# EDA.net
KiCad netlist of a schematic drawn in EasyEDA
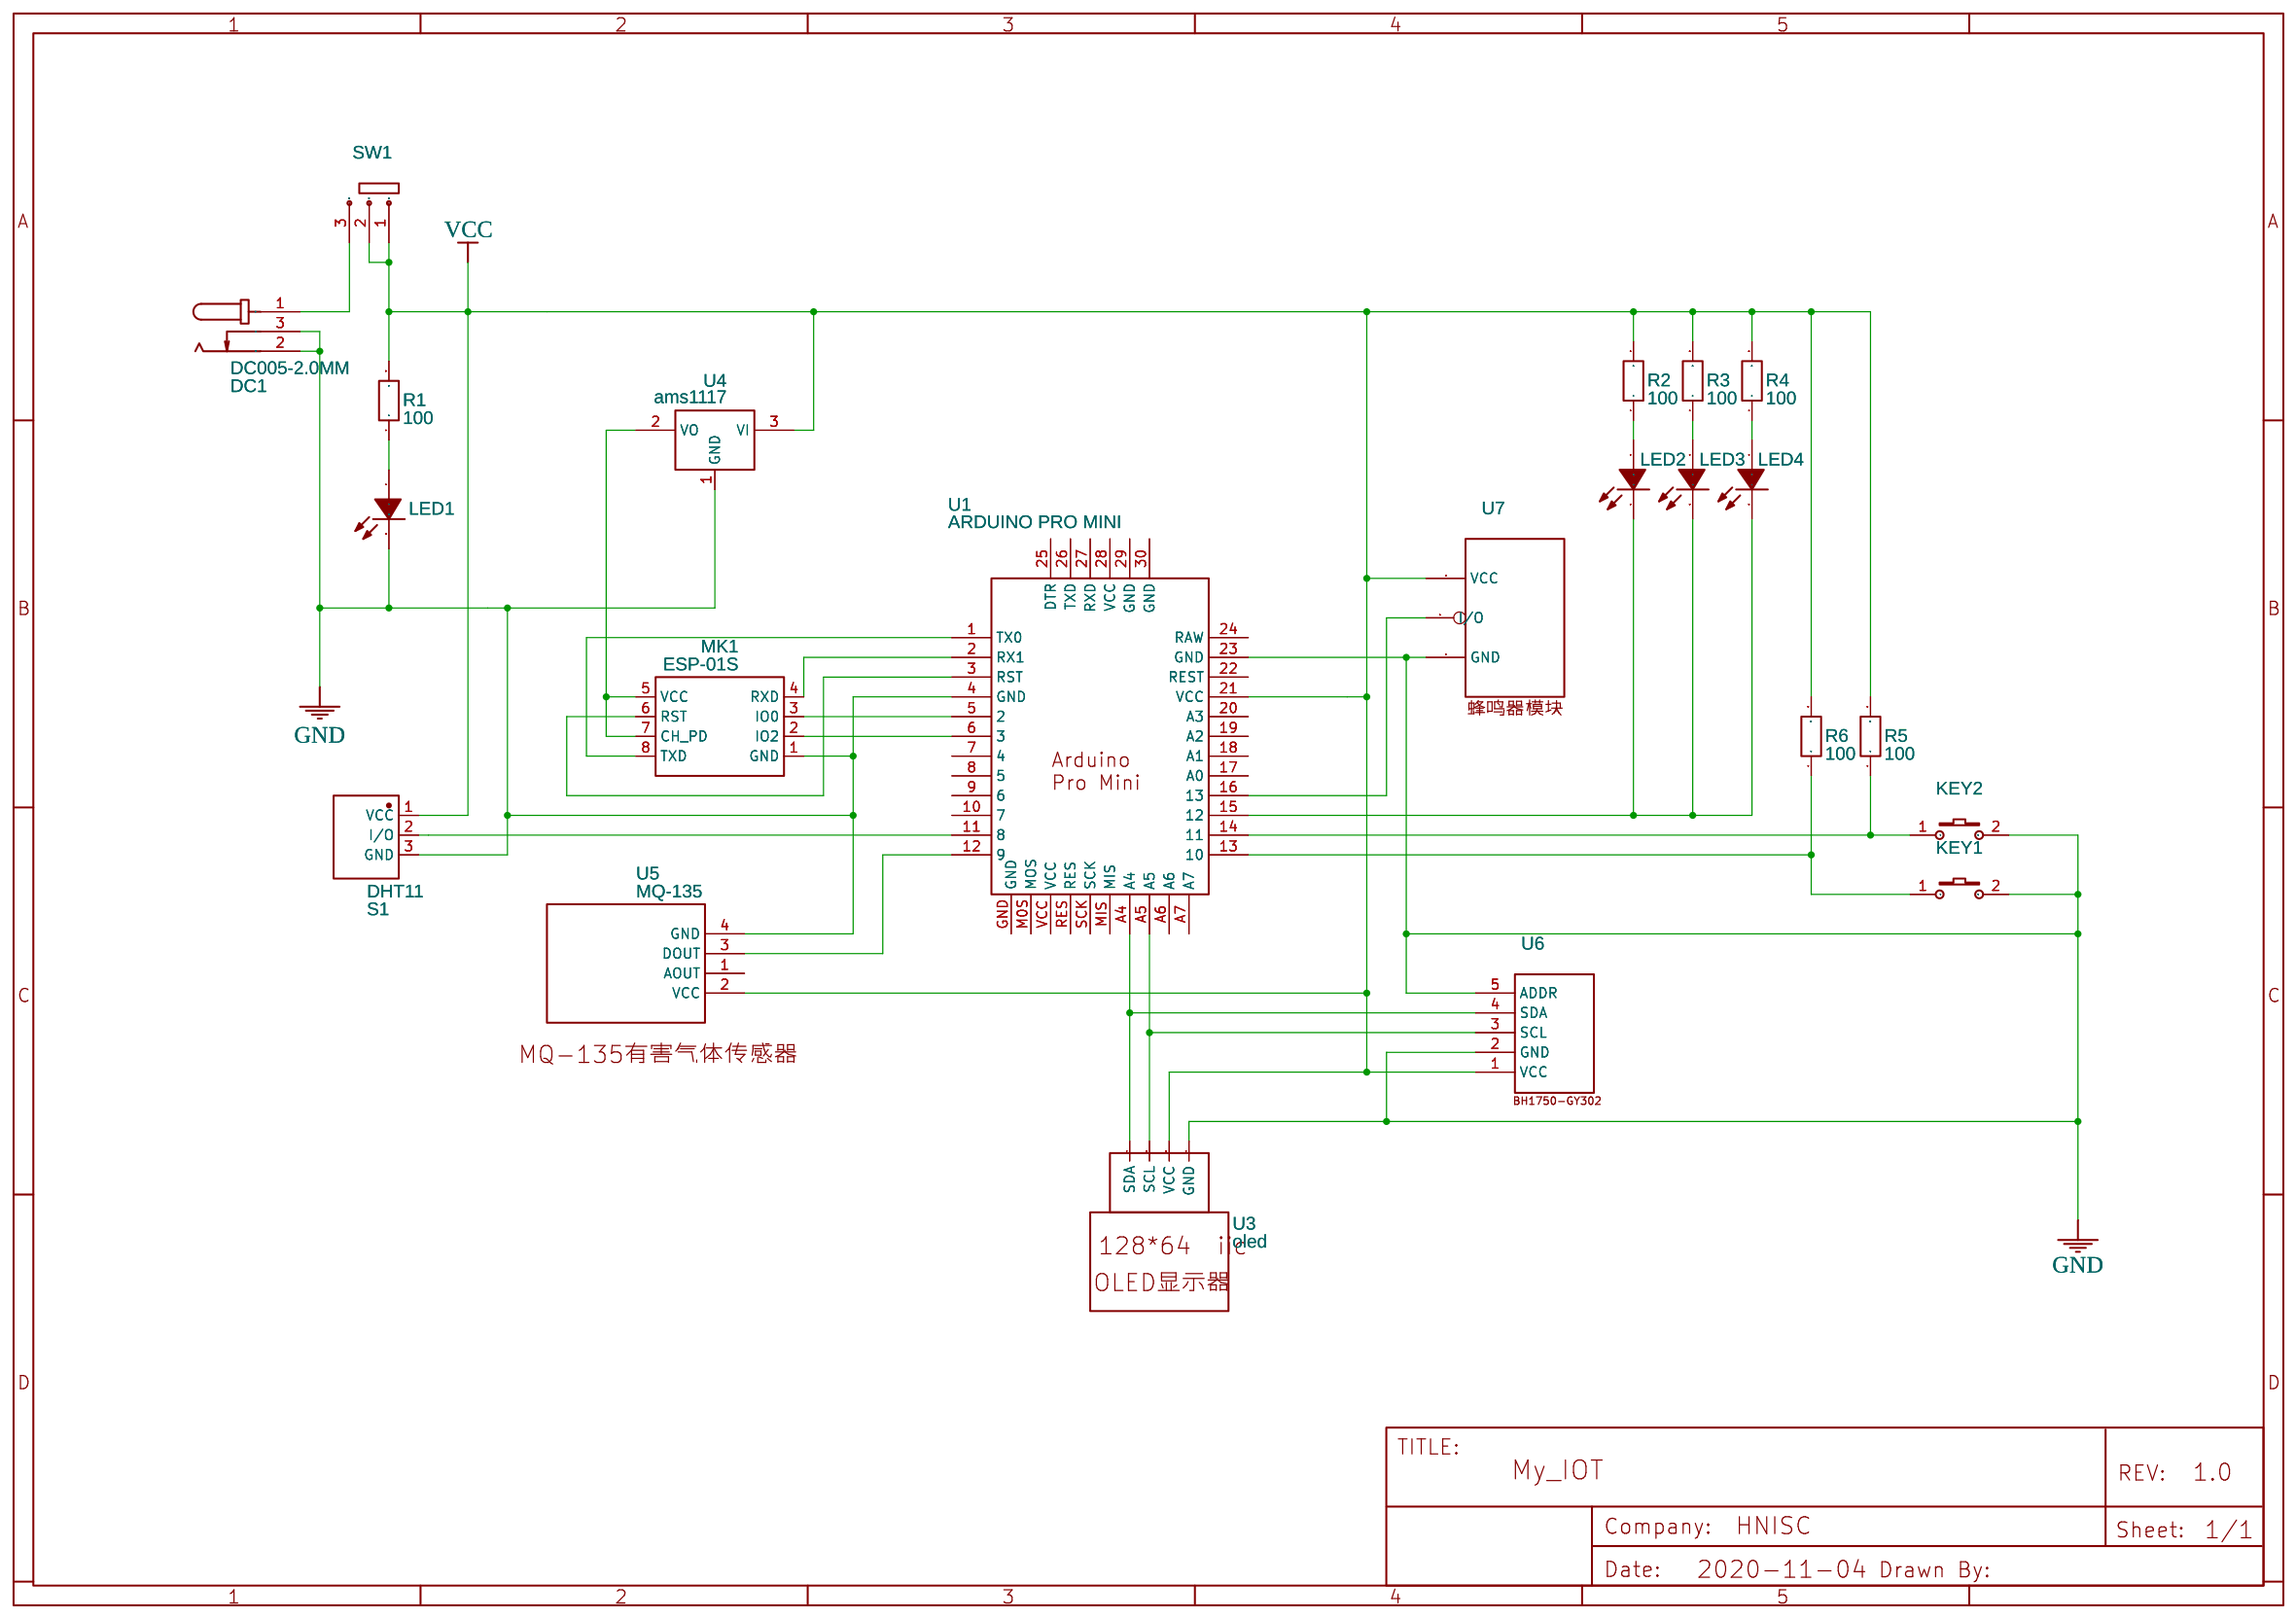
[diagram p0: schematic sheet]

(export (version "E")
  (design (tool "Eeschema 10.0.6"))
  (components
    (comp (ref "DC1")
      (value "DC005-2.0MM")
      (fields (field (name "BOM_Supplier Part") "C111567"))
      (libsource (lib "") (part "DC005-2.0MM"))
    )
    (comp (ref "KEY1")
      (value "K2-3.6×6.1_SMD")
      (fields
        (field (name "BOM_Manufacturer Part") "K2-1107ST-A4SW-06")
        (field (name "BOM_Supplier Part") "C118141")
      )
      (libsource (lib "") (part "K2-3.6×6.1_SMD"))
    )
    (comp (ref "KEY2")
      (value "K2-3.6×6.1_SMD")
      (fields
        (field (name "BOM_Manufacturer Part") "K2-1107ST-A4SW-06")
        (field (name "BOM_Supplier Part") "C118141")
      )
      (libsource (lib "") (part "K2-3.6×6.1_SMD"))
    )
    (comp (ref "LED1")
      (value "11-21/G6C-FN2P2B/2T")
      (fields (field (name "BOM_Supplier Part") "C264319"))
      (libsource (lib "") (part "11-21/G6C-FN2P2B/2T"))
    )
    (comp (ref "LED2")
      (value "11-21/G6C-FN2P2B/2T")
      (fields (field (name "BOM_Supplier Part") "C264319"))
      (libsource (lib "") (part "11-21/G6C-FN2P2B/2T"))
    )
    (comp (ref "LED3")
      (value "11-21/G6C-FN2P2B/2T")
      (fields (field (name "BOM_Supplier Part") "C264319"))
      (libsource (lib "") (part "11-21/G6C-FN2P2B/2T"))
    )
    (comp (ref "LED4")
      (value "11-21/G6C-FN2P2B/2T")
      (fields (field (name "BOM_Supplier Part") "C264319"))
      (libsource (lib "") (part "11-21/G6C-FN2P2B/2T"))
    )
    (comp (ref "MK1")
      (value "ESP-01S")
      (fields (field (name "BOM_Supplier Part") "C82893"))
      (libsource (lib "") (part "ESP-01S"))
    )
    (comp (ref "R1") (value "100") (libsource (lib "") (part "R_0603_EU")))
    (comp (ref "R2") (value "100") (libsource (lib "") (part "R_0603_EU")))
    (comp (ref "R3") (value "100") (libsource (lib "") (part "R_0603_EU")))
    (comp (ref "R4") (value "100") (libsource (lib "") (part "R_0603_EU")))
    (comp (ref "R5") (value "100") (libsource (lib "") (part "R_0603_EU")))
    (comp (ref "R6") (value "100") (libsource (lib "") (part "R_0603_EU")))
    (comp (ref "S1")
      (value "DHT11")
      (fields (field (name "BOM_Supplier Part") "E87032"))
      (libsource (lib "") (part "DHT11"))
    )
    (comp (ref "SW1")
      (value "K3-1235S-L1")
      (fields (field (name "BOM_Supplier Part") "C223838"))
      (libsource (lib "") (part "K3-1235S-L1"))
    )
    (comp (ref "U1")
      (value "ARDUINO PRO MINI")
      (fields (field (name "BOM_Manufacturer Part") "Arduino Pro Mini China"))
      (libsource (lib "") (part "ARDUINO PRO MINI"))
    )
    (comp (ref "U3") (value "oled") (libsource (lib "") (part "oled")))
    (comp (ref "U4") (value "ams1117") (libsource (lib "") (part "ams1117")))
    (comp (ref "U5") (value "MQ-135") (libsource (lib "") (part "MQ-135")))
    (comp (ref "U6") (value "BH1750光照度传感器") (libsource (lib "") (part "BH1750光照度传感器")))
    (comp (ref "U7") (value "蜂鸣器") (libsource (lib "") (part "蜂鸣器")))
  )
  (nets
    (net (code "1") (name "GND") (class "Default")
      (node (ref "DC1") (pin "2") (pinfunction "2_2") (pintype "unspecified"))
      (node (ref "DC1") (pin "3") (pinfunction "3_3") (pintype "unspecified"))
      (node (ref "KEY1") (pin "2") (pinfunction "2_2") (pintype "unspecified"))
      (node (ref "KEY2") (pin "2") (pinfunction "2_2") (pintype "unspecified"))
      (node (ref "LED1") (pin "2") (pinfunction "K_2") (pintype "unspecified"))
      (node (ref "MK1") (pin "1") (pinfunction "GND_1") (pintype "unspecified"))
      (node (ref "S1") (pin "3") (pinfunction "GND_3") (pintype "unspecified"))
      (node (ref "U1") (pin "23") (pinfunction "GND_23") (pintype "unspecified"))
      (node (ref "U1") (pin "4") (pinfunction "GND_4") (pintype "unspecified"))
      (node (ref "U3") (pin "1") (pinfunction "GND_1") (pintype "unspecified"))
      (node (ref "U4") (pin "1") (pinfunction "GND_1") (pintype "input"))
      (node (ref "U5") (pin "4") (pinfunction "GND_4") (pintype "unspecified"))
      (node (ref "U6") (pin "2") (pinfunction "GND_2") (pintype "unspecified"))
      (node (ref "U6") (pin "5") (pinfunction "ADDR_5") (pintype "unspecified"))
      (node (ref "U7") (pin "1") (pinfunction "GND_1") (pintype "unspecified"))
    )
    (net (code "2") (name "Net-(DC1-Pad1)") (class "Default")
      (node (ref "DC1") (pin "1") (pinfunction "1_1") (pintype "unspecified"))
      (node (ref "SW1") (pin "3") (pinfunction "3_3") (pintype "unspecified"))
    )
    (net (code "3") (name "Net-(LED1-A)") (class "Default")
      (node (ref "LED1") (pin "1") (pinfunction "A_1") (pintype "unspecified"))
      (node (ref "R1") (pin "1") (pinfunction "1_1") (pintype "unspecified"))
    )
    (net (code "4") (name "Net-(LED2-A)") (class "Default")
      (node (ref "LED2") (pin "1") (pinfunction "A_1") (pintype "unspecified"))
      (node (ref "R2") (pin "1") (pinfunction "1_1") (pintype "unspecified"))
    )
    (net (code "5") (name "Net-(LED2-K)") (class "Default")
      (node (ref "LED2") (pin "2") (pinfunction "K_2") (pintype "unspecified"))
      (node (ref "LED3") (pin "2") (pinfunction "K_2") (pintype "unspecified"))
      (node (ref "LED4") (pin "2") (pinfunction "K_2") (pintype "unspecified"))
      (node (ref "U1") (pin "15") (pinfunction "12_15") (pintype "unspecified"))
    )
    (net (code "6") (name "Net-(LED3-A)") (class "Default")
      (node (ref "LED3") (pin "1") (pinfunction "A_1") (pintype "unspecified"))
      (node (ref "R3") (pin "1") (pinfunction "1_1") (pintype "unspecified"))
    )
    (net (code "7") (name "Net-(LED4-A)") (class "Default")
      (node (ref "LED4") (pin "1") (pinfunction "A_1") (pintype "unspecified"))
      (node (ref "R4") (pin "1") (pinfunction "1_1") (pintype "unspecified"))
    )
    (net (code "8") (name "Net-(MK1-CH_PD)") (class "Default")
      (node (ref "MK1") (pin "5") (pinfunction "VCC_5") (pintype "unspecified"))
      (node (ref "MK1") (pin "7") (pinfunction "CH_PD_7") (pintype "unspecified"))
      (node (ref "U4") (pin "2") (pinfunction "VO_2") (pintype "unspecified"))
    )
    (net (code "9") (name "Net-(MK1-IO0)") (class "Default")
      (node (ref "MK1") (pin "3") (pinfunction "IO0_3") (pintype "unspecified"))
      (node (ref "U1") (pin "5") (pinfunction "2_5") (pintype "unspecified"))
    )
    (net (code "10") (name "Net-(MK1-IO2)") (class "Default")
      (node (ref "MK1") (pin "2") (pinfunction "IO2_2") (pintype "unspecified"))
      (node (ref "U1") (pin "6") (pinfunction "3_6") (pintype "unspecified"))
    )
    (net (code "11") (name "Net-(MK1-RST)") (class "Default")
      (node (ref "MK1") (pin "6") (pinfunction "RST_6") (pintype "unspecified"))
      (node (ref "U1") (pin "3") (pinfunction "RST_3") (pintype "unspecified"))
    )
    (net (code "12") (name "Net-(MK1-RXD)") (class "Default")
      (node (ref "MK1") (pin "4") (pinfunction "RXD_4") (pintype "unspecified"))
      (node (ref "U1") (pin "2") (pinfunction "RX1_2") (pintype "unspecified"))
    )
    (net (code "13") (name "Net-(MK1-TXD)") (class "Default")
      (node (ref "MK1") (pin "8") (pinfunction "TXD_8") (pintype "unspecified"))
      (node (ref "U1") (pin "1") (pinfunction "TX0_1") (pintype "unspecified"))
    )
    (net (code "14") (name "Net-(S1-I{slash}O)") (class "Default")
      (node (ref "S1") (pin "2") (pinfunction "I/O_2") (pintype "unspecified"))
      (node (ref "U1") (pin "11") (pinfunction "8_11") (pintype "unspecified"))
    )
    (net (code "15") (name "Net-(U1-9)") (class "Default")
      (node (ref "U1") (pin "12") (pinfunction "9_12") (pintype "unspecified"))
      (node (ref "U5") (pin "3") (pinfunction "DOUT_3") (pintype "unspecified"))
    )
    (net (code "16") (name "Net-(U1-10)") (class "Default")
      (node (ref "KEY1") (pin "1") (pinfunction "1_1") (pintype "unspecified"))
      (node (ref "R6") (pin "1") (pinfunction "1_1") (pintype "unspecified"))
      (node (ref "U1") (pin "13") (pinfunction "10_13") (pintype "unspecified"))
    )
    (net (code "17") (name "Net-(U1-11)") (class "Default")
      (node (ref "KEY2") (pin "1") (pinfunction "1_1") (pintype "unspecified"))
      (node (ref "R5") (pin "1") (pinfunction "1_1") (pintype "unspecified"))
      (node (ref "U1") (pin "14") (pinfunction "11_14") (pintype "unspecified"))
    )
    (net (code "18") (name "Net-(U1-13)") (class "Default")
      (node (ref "U1") (pin "16") (pinfunction "13_16") (pintype "unspecified"))
      (node (ref "U7") (pin "2") (pinfunction "I/O_2") (pintype "unspecified"))
    )
    (net (code "19") (name "Net-(U3-SCL)") (class "Default")
      (node (ref "U1") (pin "A5") (pinfunction "A5_A5") (pintype "unspecified"))
      (node (ref "U3") (pin "3") (pinfunction "SCL_3") (pintype "unspecified"))
      (node (ref "U6") (pin "3") (pinfunction "SCL_3") (pintype "unspecified"))
    )
    (net (code "20") (name "Net-(U3-SDA)") (class "Default")
      (node (ref "U1") (pin "A4") (pinfunction "A4_A4") (pintype "unspecified"))
      (node (ref "U3") (pin "4") (pinfunction "SDA_4") (pintype "unspecified"))
      (node (ref "U6") (pin "4") (pinfunction "SDA_4") (pintype "unspecified"))
    )
    (net (code "21") (name "VCC") (class "Default")
      (node (ref "R1") (pin "2") (pinfunction "2_2") (pintype "unspecified"))
      (node (ref "R2") (pin "2") (pinfunction "2_2") (pintype "unspecified"))
      (node (ref "R3") (pin "2") (pinfunction "2_2") (pintype "unspecified"))
      (node (ref "R4") (pin "2") (pinfunction "2_2") (pintype "unspecified"))
      (node (ref "R5") (pin "2") (pinfunction "2_2") (pintype "unspecified"))
      (node (ref "R6") (pin "2") (pinfunction "2_2") (pintype "unspecified"))
      (node (ref "S1") (pin "1") (pinfunction "VCC_1") (pintype "unspecified"))
      (node (ref "SW1") (pin "1") (pinfunction "1_1") (pintype "unspecified"))
      (node (ref "SW1") (pin "2") (pinfunction "2_2") (pintype "unspecified"))
      (node (ref "U1") (pin "21") (pinfunction "VCC_21") (pintype "unspecified"))
      (node (ref "U3") (pin "2") (pinfunction "VCC_2") (pintype "unspecified"))
      (node (ref "U4") (pin "3") (pinfunction "VI_3") (pintype "input"))
      (node (ref "U5") (pin "2") (pinfunction "VCC_2") (pintype "unspecified"))
      (node (ref "U6") (pin "1") (pinfunction "VCC_1") (pintype "unspecified"))
      (node (ref "U7") (pin "3") (pinfunction "VCC_3") (pintype "unspecified"))
    )
    (net (code "22") (name "unconnected-(U1-4-Pad7)") (class "Default")
      (node (ref "U1") (pin "7") (pinfunction "4_7") (pintype "unspecified"))
    )
    (net (code "23") (name "unconnected-(U1-5-Pad8)") (class "Default")
      (node (ref "U1") (pin "8") (pinfunction "5_8") (pintype "unspecified"))
    )
    (net (code "24") (name "unconnected-(U1-6-Pad9)") (class "Default")
      (node (ref "U1") (pin "9") (pinfunction "6_9") (pintype "unspecified"))
    )
    (net (code "25") (name "unconnected-(U1-7-Pad10)") (class "Default")
      (node (ref "U1") (pin "10") (pinfunction "7_10") (pintype "unspecified"))
    )
    (net (code "26") (name "unconnected-(U1-A0-Pad17)") (class "Default")
      (node (ref "U1") (pin "17") (pinfunction "A0_17") (pintype "unspecified"))
    )
    (net (code "27") (name "unconnected-(U1-A1-Pad18)") (class "Default")
      (node (ref "U1") (pin "18") (pinfunction "A1_18") (pintype "unspecified"))
    )
    (net (code "28") (name "unconnected-(U1-A2-Pad19)") (class "Default")
      (node (ref "U1") (pin "19") (pinfunction "A2_19") (pintype "unspecified"))
    )
    (net (code "29") (name "unconnected-(U1-A3-Pad20)") (class "Default")
      (node (ref "U1") (pin "20") (pinfunction "A3_20") (pintype "unspecified"))
    )
    (net (code "30") (name "unconnected-(U1-DTR-Pad25)") (class "Default")
      (node (ref "U1") (pin "25") (pinfunction "DTR_25") (pintype "unspecified"))
    )
    (net (code "31") (name "unconnected-(U1-GND-Pad29)") (class "Default")
      (node (ref "U1") (pin "29") (pinfunction "GND_29") (pintype "unspecified"))
    )
    (net (code "32") (name "unconnected-(U1-GND-Pad30)") (class "Default")
      (node (ref "U1") (pin "30") (pinfunction "GND_30") (pintype "unspecified"))
    )
    (net (code "33") (name "unconnected-(U1-MOS-PadM0S)") (class "Default")
      (node (ref "U1") (pin "M0S") (pinfunction "MOS_M0S") (pintype "unspecified"))
    )
    (net (code "34") (name "unconnected-(U1-PadA6)") (class "Default")
      (node (ref "U1") (pin "A6") (pinfunction "A6_A6") (pintype "unspecified"))
    )
    (net (code "35") (name "unconnected-(U1-PadA7)") (class "Default")
      (node (ref "U1") (pin "A7") (pinfunction "A7_A7") (pintype "unspecified"))
    )
    (net (code "36") (name "unconnected-(U1-PadGND)") (class "Default")
      (node (ref "U1") (pin "GND") (pinfunction "GND_GND") (pintype "unspecified"))
    )
    (net (code "37") (name "unconnected-(U1-PadMIS)") (class "Default")
      (node (ref "U1") (pin "MIS") (pinfunction "MIS_MIS") (pintype "unspecified"))
    )
    (net (code "38") (name "unconnected-(U1-PadRES)") (class "Default")
      (node (ref "U1") (pin "RES") (pinfunction "RES_RES") (pintype "unspecified"))
    )
    (net (code "39") (name "unconnected-(U1-PadSCK)") (class "Default")
      (node (ref "U1") (pin "SCK") (pinfunction "SCK_SCK") (pintype "unspecified"))
    )
    (net (code "40") (name "unconnected-(U1-PadVCC)") (class "Default")
      (node (ref "U1") (pin "VCC") (pinfunction "VCC_VCC") (pintype "unspecified"))
    )
    (net (code "41") (name "unconnected-(U1-RAW-Pad24)") (class "Default")
      (node (ref "U1") (pin "24") (pinfunction "RAW_24") (pintype "unspecified"))
    )
    (net (code "42") (name "unconnected-(U1-REST-Pad22)") (class "Default")
      (node (ref "U1") (pin "22") (pinfunction "REST_22") (pintype "unspecified"))
    )
    (net (code "43") (name "unconnected-(U1-RXD-Pad27)") (class "Default")
      (node (ref "U1") (pin "27") (pinfunction "RXD_27") (pintype "unspecified"))
    )
    (net (code "44") (name "unconnected-(U1-TXD-Pad26)") (class "Default")
      (node (ref "U1") (pin "26") (pinfunction "TXD_26") (pintype "unspecified"))
    )
    (net (code "45") (name "unconnected-(U1-VCC-Pad28)") (class "Default")
      (node (ref "U1") (pin "28") (pinfunction "VCC_28") (pintype "unspecified"))
    )
    (net (code "46") (name "unconnected-(U5-AOUT-Pad1)") (class "Default")
      (node (ref "U5") (pin "1") (pinfunction "AOUT_1") (pintype "unspecified"))
    )
  )
)
